# MGT_Banks_115-116.net
KiCad netlist of a schematic drawn in Altium Designer
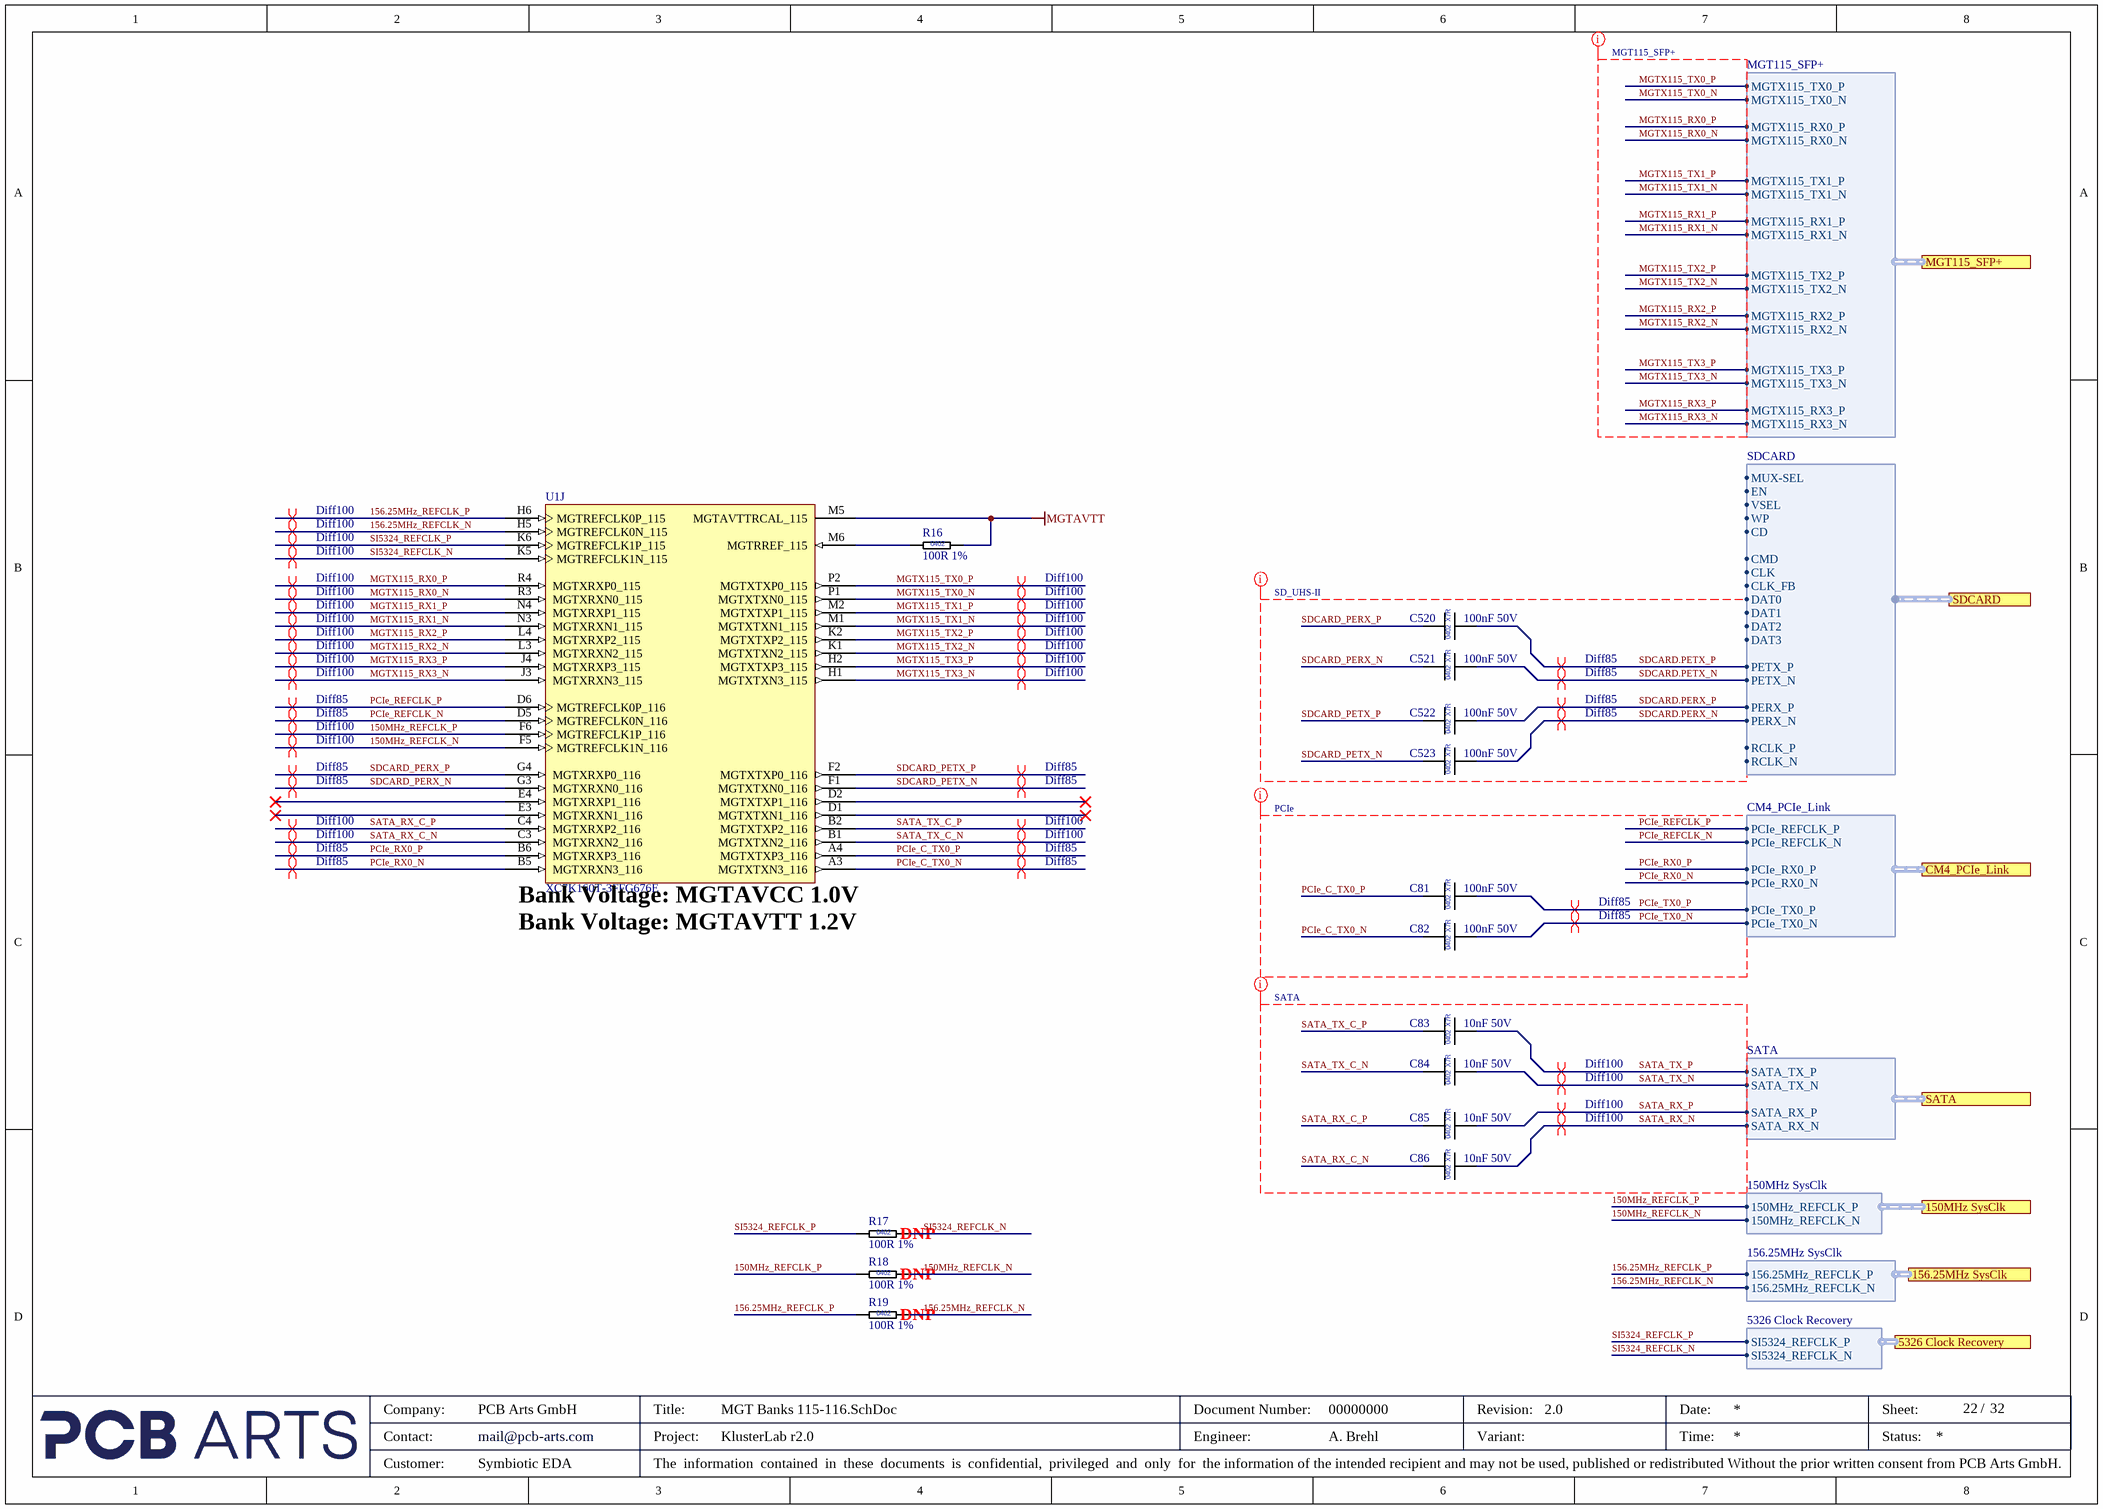
[diagram p0: MGT Banks 115-116.SchDoc]

(export (version "E")
  (design (tool "Eeschema 10.0.6"))
  (components
    (comp (ref "C81")
      (value "100nF 50V")
      (footprint "Cap:CAP_0402_L")
      (description "Multilayer Ceramic Capacitors MLCC - SMD/SMT 0402 50VDC")
      (libsource (lib "Cap") (part "CAP_0402_100nF_50V"))
    )
    (comp (ref "C82")
      (value "100nF 50V")
      (footprint "Cap:CAP_0402_L")
      (description "Multilayer Ceramic Capacitors MLCC - SMD/SMT 0402 50VDC")
      (libsource (lib "Cap") (part "CAP_0402_100nF_50V"))
    )
    (comp (ref "C83")
      (value "10nF 50V")
      (footprint "Cap:CAP_0402_L")
      (description "Multilayer Ceramic Capacitors MLCC - SMD/SMT 0402 50VDC")
      (libsource (lib "Cap") (part "CAP_0402_10nF_50V"))
    )
    (comp (ref "C84")
      (value "10nF 50V")
      (footprint "Cap:CAP_0402_L")
      (description "Multilayer Ceramic Capacitors MLCC - SMD/SMT 0402 50VDC")
      (libsource (lib "Cap") (part "CAP_0402_10nF_50V"))
    )
    (comp (ref "C85")
      (value "10nF 50V")
      (footprint "Cap:CAP_0402_L")
      (description "Multilayer Ceramic Capacitors MLCC - SMD/SMT 0402 50VDC")
      (libsource (lib "Cap") (part "CAP_0402_10nF_50V"))
    )
    (comp (ref "C86")
      (value "10nF 50V")
      (footprint "Cap:CAP_0402_L")
      (description "Multilayer Ceramic Capacitors MLCC - SMD/SMT 0402 50VDC")
      (libsource (lib "Cap") (part "CAP_0402_10nF_50V"))
    )
    (comp (ref "C520")
      (value "100nF 50V")
      (footprint "Cap:CAP_0402_L")
      (description "Multilayer Ceramic Capacitors MLCC - SMD/SMT 0402 50VDC")
      (libsource (lib "Cap") (part "CAP_0402_100nF_50V"))
    )
    (comp (ref "C521")
      (value "100nF 50V")
      (footprint "Cap:CAP_0402_L")
      (description "Multilayer Ceramic Capacitors MLCC - SMD/SMT 0402 50VDC")
      (libsource (lib "Cap") (part "CAP_0402_100nF_50V"))
    )
    (comp (ref "C522")
      (value "100nF 50V")
      (footprint "Cap:CAP_0402_L")
      (description "Multilayer Ceramic Capacitors MLCC - SMD/SMT 0402 50VDC")
      (libsource (lib "Cap") (part "CAP_0402_100nF_50V"))
    )
    (comp (ref "C523")
      (value "100nF 50V")
      (footprint "Cap:CAP_0402_L")
      (description "Multilayer Ceramic Capacitors MLCC - SMD/SMT 0402 50VDC")
      (libsource (lib "Cap") (part "CAP_0402_100nF_50V"))
    )
    (comp (ref "R16")
      (value "100R 1%")
      (footprint "Res:RES_0402_L")
      (description "Thick Film Resistors - SMD 100Ohm 1%")
      (libsource (lib "Res") (part "RES_0402_100R_1%"))
    )
    (comp (ref "R17")
      (value "100R 1%")
      (footprint "Res:RES_0402_L")
      (description "Thick Film Resistors - SMD 100Ohm 1%")
      (libsource (lib "Res") (part "RES_0402_100R_1%"))
    )
    (comp (ref "R18")
      (value "100R 1%")
      (footprint "Res:RES_0402_L")
      (description "Thick Film Resistors - SMD 100Ohm 1%")
      (libsource (lib "Res") (part "RES_0402_100R_1%"))
    )
    (comp (ref "R19")
      (value "100R 1%")
      (footprint "Res:RES_0402_L")
      (description "Thick Film Resistors - SMD 100Ohm 1%")
      (libsource (lib "Res") (part "RES_0402_100R_1%"))
    )
    (comp (ref "U1")
      (value "XC7K160T-3FFG676E")
      (footprint "Digital:BGA100P2700X2700X317-676N")
      (description "Kintex-7 FPGA, 400 User I/Os, 8 GTX, 676-Ball BGA, Speed Grade 3, Extended Grade, Pb-Free")
      (libsource (lib "Digital") (part "XC7K160T-3FFG676E_Kintex-7 FPGA, 400 User I/Os, 8 GTX, FFG676"))
    )
  )
  (nets
    (net (code "11") (name "/150MHz_REFCLK_N") (class "Default")
      (node (ref "R18") (pin "2") (pinfunction "2_2") (pintype "passive"))
      (node (ref "U1") (pin "F5") (pinfunction "MGTREFCLK1N_116_F5") (pintype "input"))
    )
    (net (code "12") (name "/150MHz_REFCLK_P") (class "Default")
      (node (ref "R18") (pin "1") (pinfunction "1_1") (pintype "passive"))
      (node (ref "U1") (pin "F6") (pinfunction "MGTREFCLK1P_116_F6") (pintype "input"))
    )
    (net (code "13") (name "/156.25MHz_REFCLK_N") (class "Default")
      (node (ref "R19") (pin "2") (pinfunction "2_2") (pintype "passive"))
      (node (ref "U1") (pin "H5") (pinfunction "MGTREFCLK0N_115_H5") (pintype "input"))
    )
    (net (code "14") (name "/156.25MHz_REFCLK_P") (class "Default")
      (node (ref "R19") (pin "1") (pinfunction "1_1") (pintype "passive"))
      (node (ref "U1") (pin "H6") (pinfunction "MGTREFCLK0P_115_H6") (pintype "input"))
    )
    (net (code "15") (name "/MGTX115_RX0_N") (class "Default")
      (node (ref "U1") (pin "R3") (pinfunction "MGTXRXN0_115_R3") (pintype "input"))
    )
    (net (code "16") (name "/MGTX115_RX0_P") (class "Default")
      (node (ref "U1") (pin "R4") (pinfunction "MGTXRXP0_115_R4") (pintype "input"))
    )
    (net (code "17") (name "/MGTX115_RX1_N") (class "Default")
      (node (ref "U1") (pin "N3") (pinfunction "MGTXRXN1_115_N3") (pintype "input"))
    )
    (net (code "18") (name "/MGTX115_RX1_P") (class "Default")
      (node (ref "U1") (pin "N4") (pinfunction "MGTXRXP1_115_N4") (pintype "input"))
    )
    (net (code "19") (name "/MGTX115_RX2_N") (class "Default")
      (node (ref "U1") (pin "L3") (pinfunction "MGTXRXN2_115_L3") (pintype "input"))
    )
    (net (code "20") (name "/MGTX115_RX2_P") (class "Default")
      (node (ref "U1") (pin "L4") (pinfunction "MGTXRXP2_115_L4") (pintype "input"))
    )
    (net (code "21") (name "/MGTX115_RX3_N") (class "Default")
      (node (ref "U1") (pin "J3") (pinfunction "MGTXRXN3_115_J3") (pintype "input"))
    )
    (net (code "22") (name "/MGTX115_RX3_P") (class "Default")
      (node (ref "U1") (pin "J4") (pinfunction "MGTXRXP3_115_J4") (pintype "input"))
    )
    (net (code "23") (name "/MGTX115_TX0_N") (class "Default")
      (node (ref "U1") (pin "P1") (pinfunction "MGTXTXN0_115_P1") (pintype "output"))
    )
    (net (code "24") (name "/MGTX115_TX0_P") (class "Default")
      (node (ref "U1") (pin "P2") (pinfunction "MGTXTXP0_115_P2") (pintype "output"))
    )
    (net (code "25") (name "/MGTX115_TX1_N") (class "Default")
      (node (ref "U1") (pin "M1") (pinfunction "MGTXTXN1_115_M1") (pintype "output"))
    )
    (net (code "26") (name "/MGTX115_TX1_P") (class "Default")
      (node (ref "U1") (pin "M2") (pinfunction "MGTXTXP1_115_M2") (pintype "output"))
    )
    (net (code "27") (name "/MGTX115_TX2_N") (class "Default")
      (node (ref "U1") (pin "K1") (pinfunction "MGTXTXN2_115_K1") (pintype "output"))
    )
    (net (code "28") (name "/MGTX115_TX2_P") (class "Default")
      (node (ref "U1") (pin "K2") (pinfunction "MGTXTXP2_115_K2") (pintype "output"))
    )
    (net (code "29") (name "/MGTX115_TX3_N") (class "Default")
      (node (ref "U1") (pin "H1") (pinfunction "MGTXTXN3_115_H1") (pintype "output"))
    )
    (net (code "30") (name "/MGTX115_TX3_P") (class "Default")
      (node (ref "U1") (pin "H2") (pinfunction "MGTXTXP3_115_H2") (pintype "output"))
    )
    (net (code "31") (name "/PCIe_C_TX0_N") (class "Default")
      (node (ref "C82") (pin "1") (pinfunction "1_1") (pintype "passive"))
      (node (ref "U1") (pin "A3") (pinfunction "MGTXTXN3_116_A3") (pintype "output"))
    )
    (net (code "32") (name "/PCIe_C_TX0_P") (class "Default")
      (node (ref "C81") (pin "1") (pinfunction "1_1") (pintype "passive"))
      (node (ref "U1") (pin "A4") (pinfunction "MGTXTXP3_116_A4") (pintype "output"))
    )
    (net (code "33") (name "/PCIe_REFCLK_N") (class "Default")
      (node (ref "U1") (pin "D5") (pinfunction "MGTREFCLK0N_116_D5") (pintype "input"))
    )
    (net (code "34") (name "/PCIe_REFCLK_P") (class "Default")
      (node (ref "U1") (pin "D6") (pinfunction "MGTREFCLK0P_116_D6") (pintype "input"))
    )
    (net (code "35") (name "/PCIe_RX0_N") (class "Default")
      (node (ref "U1") (pin "B5") (pinfunction "MGTXRXN3_116_B5") (pintype "input"))
    )
    (net (code "36") (name "/PCIe_RX0_P") (class "Default")
      (node (ref "U1") (pin "B6") (pinfunction "MGTXRXP3_116_B6") (pintype "input"))
    )
    (net (code "37") (name "/PCIe_TX0_N") (class "Default")
      (node (ref "C82") (pin "2") (pinfunction "2_2") (pintype "passive"))
    )
    (net (code "38") (name "/PCIe_TX0_P") (class "Default")
      (node (ref "C81") (pin "2") (pinfunction "2_2") (pintype "passive"))
    )
    (net (code "39") (name "/SATA_RX_C_N") (class "Default")
      (node (ref "C86") (pin "1") (pinfunction "1_1") (pintype "passive"))
      (node (ref "U1") (pin "C3") (pinfunction "MGTXRXN2_116_C3") (pintype "input"))
    )
    (net (code "40") (name "/SATA_RX_C_P") (class "Default")
      (node (ref "C85") (pin "1") (pinfunction "1_1") (pintype "passive"))
      (node (ref "U1") (pin "C4") (pinfunction "MGTXRXP2_116_C4") (pintype "input"))
    )
    (net (code "41") (name "/SATA_RX_N") (class "Default")
      (node (ref "C86") (pin "2") (pinfunction "2_2") (pintype "passive"))
    )
    (net (code "42") (name "/SATA_RX_P") (class "Default")
      (node (ref "C85") (pin "2") (pinfunction "2_2") (pintype "passive"))
    )
    (net (code "43") (name "/SATA_TX_C_N") (class "Default")
      (node (ref "C84") (pin "1") (pinfunction "1_1") (pintype "passive"))
      (node (ref "U1") (pin "B1") (pinfunction "MGTXTXN2_116_B1") (pintype "output"))
    )
    (net (code "44") (name "/SATA_TX_C_P") (class "Default")
      (node (ref "C83") (pin "1") (pinfunction "1_1") (pintype "passive"))
      (node (ref "U1") (pin "B2") (pinfunction "MGTXTXP2_116_B2") (pintype "output"))
    )
    (net (code "45") (name "/SATA_TX_N") (class "Default")
      (node (ref "C84") (pin "2") (pinfunction "2_2") (pintype "passive"))
    )
    (net (code "46") (name "/SATA_TX_P") (class "Default")
      (node (ref "C83") (pin "2") (pinfunction "2_2") (pintype "passive"))
    )
    (net (code "47") (name "/SDCARD.PERX_N") (class "Default")
      (node (ref "C523") (pin "2") (pinfunction "2_2") (pintype "passive"))
    )
    (net (code "48") (name "/SDCARD.PERX_P") (class "Default")
      (node (ref "C522") (pin "2") (pinfunction "2_2") (pintype "passive"))
    )
    (net (code "49") (name "/SDCARD.PETX_N") (class "Default")
      (node (ref "C521") (pin "2") (pinfunction "2_2") (pintype "passive"))
    )
    (net (code "50") (name "/SDCARD.PETX_P") (class "Default")
      (node (ref "C520") (pin "2") (pinfunction "2_2") (pintype "passive"))
    )
    (net (code "51") (name "/SDCARD_PERX_N") (class "Default")
      (node (ref "C521") (pin "1") (pinfunction "1_1") (pintype "passive"))
      (node (ref "U1") (pin "G3") (pinfunction "MGTXRXN0_116_G3") (pintype "input"))
    )
    (net (code "52") (name "/SDCARD_PERX_P") (class "Default")
      (node (ref "C520") (pin "1") (pinfunction "1_1") (pintype "passive"))
      (node (ref "U1") (pin "G4") (pinfunction "MGTXRXP0_116_G4") (pintype "input"))
    )
    (net (code "53") (name "/SDCARD_PETX_N") (class "Default")
      (node (ref "C523") (pin "1") (pinfunction "1_1") (pintype "passive"))
      (node (ref "U1") (pin "F1") (pinfunction "MGTXTXN0_116_F1") (pintype "output"))
    )
    (net (code "54") (name "/SDCARD_PETX_P") (class "Default")
      (node (ref "C522") (pin "1") (pinfunction "1_1") (pintype "passive"))
      (node (ref "U1") (pin "F2") (pinfunction "MGTXTXP0_116_F2") (pintype "output"))
    )
    (net (code "55") (name "/SI5324_REFCLK_N") (class "Default")
      (node (ref "R17") (pin "2") (pinfunction "2_2") (pintype "passive"))
      (node (ref "U1") (pin "K5") (pinfunction "MGTREFCLK1N_115_K5") (pintype "input"))
    )
    (net (code "56") (name "/SI5324_REFCLK_P") (class "Default")
      (node (ref "R17") (pin "1") (pinfunction "1_1") (pintype "passive"))
      (node (ref "U1") (pin "K6") (pinfunction "MGTREFCLK1P_115_K6") (pintype "input"))
    )
    (net (code "64") (name "MGTAVTT") (class "Default")
      (node (ref "R16") (pin "2") (pinfunction "2_2") (pintype "passive"))
      (node (ref "U1") (pin "M5") (pinfunction "MGTAVTTRCAL_115_M5") (pintype "passive"))
    )
    (net (code "65") (name "Net-(U1J-MGTRREF_115)") (class "Default")
      (node (ref "R16") (pin "1") (pinfunction "1_1") (pintype "passive"))
      (node (ref "U1") (pin "M6") (pinfunction "MGTRREF_115_M6") (pintype "input"))
    )
    (net (code "66") (name "unconnected-(U1J-MGTXRXN1_116-PadE3)") (class "Default")
      (node (ref "U1") (pin "E3") (pinfunction "MGTXRXN1_116_E3") (pintype "input+no_connect"))
    )
    (net (code "67") (name "unconnected-(U1J-MGTXRXP1_116-PadE4)") (class "Default")
      (node (ref "U1") (pin "E4") (pinfunction "MGTXRXP1_116_E4") (pintype "input+no_connect"))
    )
    (net (code "68") (name "unconnected-(U1J-MGTXTXN1_116-PadD1)") (class "Default")
      (node (ref "U1") (pin "D1") (pinfunction "MGTXTXN1_116_D1") (pintype "output+no_connect"))
    )
    (net (code "69") (name "unconnected-(U1J-MGTXTXP1_116-PadD2)") (class "Default")
      (node (ref "U1") (pin "D2") (pinfunction "MGTXTXP1_116_D2") (pintype "output+no_connect"))
    )
  )
)
